# Sheet2.net
KiCad netlist of a schematic drawn in Altium Designer
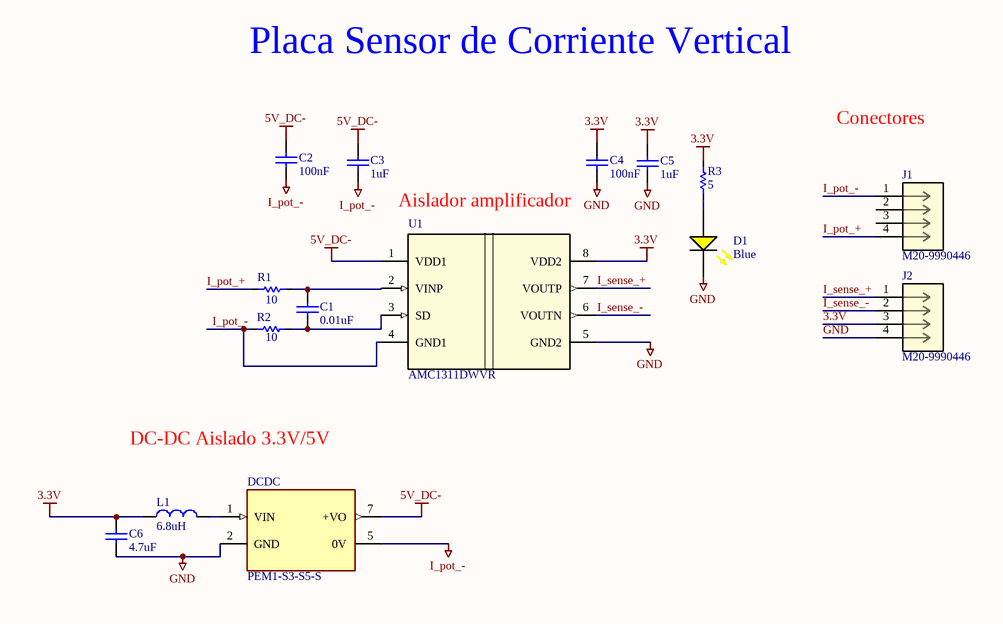
[diagram p0: Sheet2.SchDoc]

(export (version "E")
  (design (tool "Eeschema 10.0.6"))
  (components
    (comp (ref "C1")
      (value "0.01uF")
      (footprint "CAP_0603")
      (description "0.1µF ±10% 50V Ceramic Capacitor X7R 0603 (1608 Metric)")
      (fields (field (name "MF") "KEMET") (field (name "CREATED") "2020_06_15_DAarancibia"))
      (libsource (lib "Schlib1") (part "Cap_0603"))
    )
    (comp (ref "C2")
      (value "100nF")
      (footprint "CAP_0603")
      (description "0.1µF ±10% 50V Ceramic Capacitor X7R 0603 (1608 Metric)")
      (fields (field (name "MF") "KEMET") (field (name "CREATED") "2020_06_15_DAarancibia"))
      (libsource (lib "Schlib1") (part "Cap_0603"))
    )
    (comp (ref "C3")
      (value "1uF")
      (footprint "CAP_0603")
      (description "0.1µF ±10% 50V Ceramic Capacitor X7R 0603 (1608 Metric)")
      (fields (field (name "MF") "KEMET") (field (name "CREATED") "2020_06_15_DAarancibia"))
      (libsource (lib "Schlib1") (part "Cap_0603"))
    )
    (comp (ref "C4")
      (value "100nF")
      (footprint "CAP_0603")
      (description "0.1µF ±10% 50V Ceramic Capacitor X7R 0603 (1608 Metric)")
      (fields (field (name "MF") "KEMET") (field (name "CREATED") "2020_06_15_DAarancibia"))
      (libsource (lib "Schlib1") (part "Cap_0603"))
    )
    (comp (ref "C5")
      (value "1uF")
      (footprint "CAP_0603")
      (description "0.1µF ±10% 50V Ceramic Capacitor X7R 0603 (1608 Metric)")
      (fields (field (name "MF") "KEMET") (field (name "CREATED") "2020_06_15_DAarancibia"))
      (libsource (lib "Schlib1") (part "Cap_0603"))
    )
    (comp (ref "C6")
      (value "4.7uF")
      (footprint "CAP_0805")
      (description "0.1µF ±10% 50V Ceramic Capacitor X7R 0805 (2012 Metric)")
      (fields (field (name "MF") "KEMET") (field (name "CREATED") "2020_06_15_DAarancibia"))
      (libsource (lib "Schlib1") (part "Cap_0805"))
    )
    (comp (ref "D1")
      (value "Blue")
      (footprint "LED_0603_Yellow")
      (description "Yellow 590nm LED Indication - Discrete 2V 0603 (1608 Metric)")
      (fields (field (name "MF") "Würth Elektronik") (field (name "CREATED") "2020_07_06_DAarancibia"))
      (libsource (lib "Schlib1") (part "Led_0603_Yellow"))
    )
    (comp (ref "DCDC")
      (value "PEM1-S3-S5-S")
      (footprint "CONV_PEM1-S3-S5-S")
      (description "12 Vdc, 0.083 A, 1 W, 10.8~13.2 Vdc Input Range")
      (libsource (lib "Schlib1") (part "PEM1-S3-S5-S"))
    )
    (comp (ref "J1")
      (value "M20-9990446")
      (footprint "CONN_M20_4_HRW")
      (description "No Description Available")
      (libsource (lib "Schlib1") (part "M20-9990446"))
    )
    (comp (ref "J2")
      (value "M20-9990446")
      (footprint "CONN_M20_4_HRW")
      (description "No Description Available")
      (libsource (lib "Schlib1") (part "M20-9990446"))
    )
    (comp (ref "L1")
      (value "6.8uH")
      (footprint "INDUCTOR_1210")
      (description "10µH Unshielded Wirewound Inductor 700mA 350mOhm Max 1210 (3225 Metric)")
      (fields (field (name "MF") "Taiyo Yuden") (field (name "CREATED") "2020_07_06_DAarancibia"))
      (libsource (lib "Schlib1") (part "Inductor_1210"))
    )
    (comp (ref "R1")
      (value "10")
      (footprint "RES_0603")
      (fields
        (field (name "MF") "Panasonic Electronic Components")
        (field (name "CREATED") "2020_06_15_DAarancibia")
      )
      (libsource (lib "Schlib1") (part "Res_0603"))
    )
    (comp (ref "R2")
      (value "10")
      (footprint "RES_0603")
      (fields
        (field (name "MF") "Panasonic Electronic Components")
        (field (name "CREATED") "2020_06_15_DAarancibia")
      )
      (libsource (lib "Schlib1") (part "Res_0603"))
    )
    (comp (ref "R3")
      (value "5")
      (footprint "RES_0603")
      (fields
        (field (name "MF") "Panasonic Electronic Components")
        (field (name "CREATED") "2020_06_15_DAarancibia")
      )
      (libsource (lib "Schlib1") (part "Res_0603"))
    )
    (comp (ref "U1")
      (value "AMC1311DWVR")
      (footprint "DWV0008A")
      (description "No Description Available")
      (libsource (lib "Schlib1") (part "AMC1311DWVR"))
    )
  )
  (nets
    (net (code "1") (name "/I_pot_+") (class "Default")
      (node (ref "J1") (pin "4") (pinfunction "4_4") (pintype "passive"))
      (node (ref "R1") (pin "2") (pinfunction "2_2") (pintype "passive"))
    )
    (net (code "2") (name "/I_sense_+") (class "Default")
      (node (ref "J2") (pin "1") (pinfunction "1_1") (pintype "passive"))
      (node (ref "U1") (pin "7") (pinfunction "VOUTP_7") (pintype "output"))
    )
    (net (code "3") (name "/I_sense_-") (class "Default")
      (node (ref "J2") (pin "2") (pinfunction "2_2") (pintype "passive"))
      (node (ref "U1") (pin "6") (pinfunction "VOUTN_6") (pintype "output"))
    )
    (net (code "4") (name "3.3V") (class "Default")
      (node (ref "C4") (pin "1") (pinfunction "1_1") (pintype "passive"))
      (node (ref "C5") (pin "1") (pinfunction "1_1") (pintype "passive"))
      (node (ref "C6") (pin "1") (pinfunction "1_1") (pintype "passive"))
      (node (ref "J2") (pin "3") (pinfunction "3_3") (pintype "passive"))
      (node (ref "L1") (pin "1") (pinfunction "1_1") (pintype "passive"))
      (node (ref "R3") (pin "2") (pinfunction "2_2") (pintype "passive"))
      (node (ref "U1") (pin "8") (pinfunction "VDD2_8") (pintype "power_in"))
    )
    (net (code "5") (name "5V_DC-") (class "Default")
      (node (ref "C2") (pin "1") (pinfunction "1_1") (pintype "passive"))
      (node (ref "C3") (pin "1") (pinfunction "1_1") (pintype "passive"))
      (node (ref "DCDC") (pin "7") (pinfunction "+VO_7") (pintype "output"))
      (node (ref "U1") (pin "1") (pinfunction "VDD1_1") (pintype "power_in"))
    )
    (net (code "6") (name "GND") (class "Default")
      (node (ref "C4") (pin "2") (pinfunction "2_2") (pintype "passive"))
      (node (ref "C5") (pin "2") (pinfunction "2_2") (pintype "passive"))
      (node (ref "C6") (pin "2") (pinfunction "2_2") (pintype "passive"))
      (node (ref "D1") (pin "2") (pinfunction "K_2") (pintype "passive"))
      (node (ref "DCDC") (pin "2") (pinfunction "GND_2") (pintype "power_in"))
      (node (ref "J2") (pin "4") (pinfunction "4_4") (pintype "passive"))
      (node (ref "U1") (pin "5") (pinfunction "GND2_5") (pintype "power_in"))
    )
    (net (code "7") (name "I_pot_-") (class "Default")
      (node (ref "C2") (pin "2") (pinfunction "2_2") (pintype "passive"))
      (node (ref "C3") (pin "2") (pinfunction "2_2") (pintype "passive"))
      (node (ref "DCDC") (pin "5") (pinfunction "0V_5") (pintype "power_in"))
      (node (ref "J1") (pin "1") (pinfunction "1_1") (pintype "passive"))
      (node (ref "R2") (pin "2") (pinfunction "2_2") (pintype "passive"))
      (node (ref "U1") (pin "4") (pinfunction "GND1_4") (pintype "power_in"))
    )
    (net (code "8") (name "Net-(D1-A)") (class "Default")
      (node (ref "D1") (pin "1") (pinfunction "A_1") (pintype "passive"))
      (node (ref "R3") (pin "1") (pinfunction "1_1") (pintype "passive"))
    )
    (net (code "9") (name "Net-(DCDC-VIN)") (class "Default")
      (node (ref "DCDC") (pin "1") (pinfunction "VIN_1") (pintype "input"))
      (node (ref "L1") (pin "2") (pinfunction "2_2") (pintype "passive"))
    )
    (net (code "10") (name "Net-(U1-SD)") (class "Default")
      (node (ref "C1") (pin "2") (pinfunction "2_2") (pintype "passive"))
      (node (ref "R2") (pin "1") (pinfunction "1_1") (pintype "passive"))
      (node (ref "U1") (pin "3") (pinfunction "SD_3") (pintype "input"))
    )
    (net (code "11") (name "Net-(U1-VINP)") (class "Default")
      (node (ref "C1") (pin "1") (pinfunction "1_1") (pintype "passive"))
      (node (ref "R1") (pin "1") (pinfunction "1_1") (pintype "passive"))
      (node (ref "U1") (pin "2") (pinfunction "VINP_2") (pintype "input"))
    )
    (net (code "12") (name "unconnected-(J1-Pad2)") (class "Default")
      (node (ref "J1") (pin "2") (pinfunction "2_2") (pintype "passive"))
    )
    (net (code "13") (name "unconnected-(J1-Pad3)") (class "Default")
      (node (ref "J1") (pin "3") (pinfunction "3_3") (pintype "passive"))
    )
  )
)
